# CatchTheLED.net
KiCad netlist of a schematic drawn in EAGLE
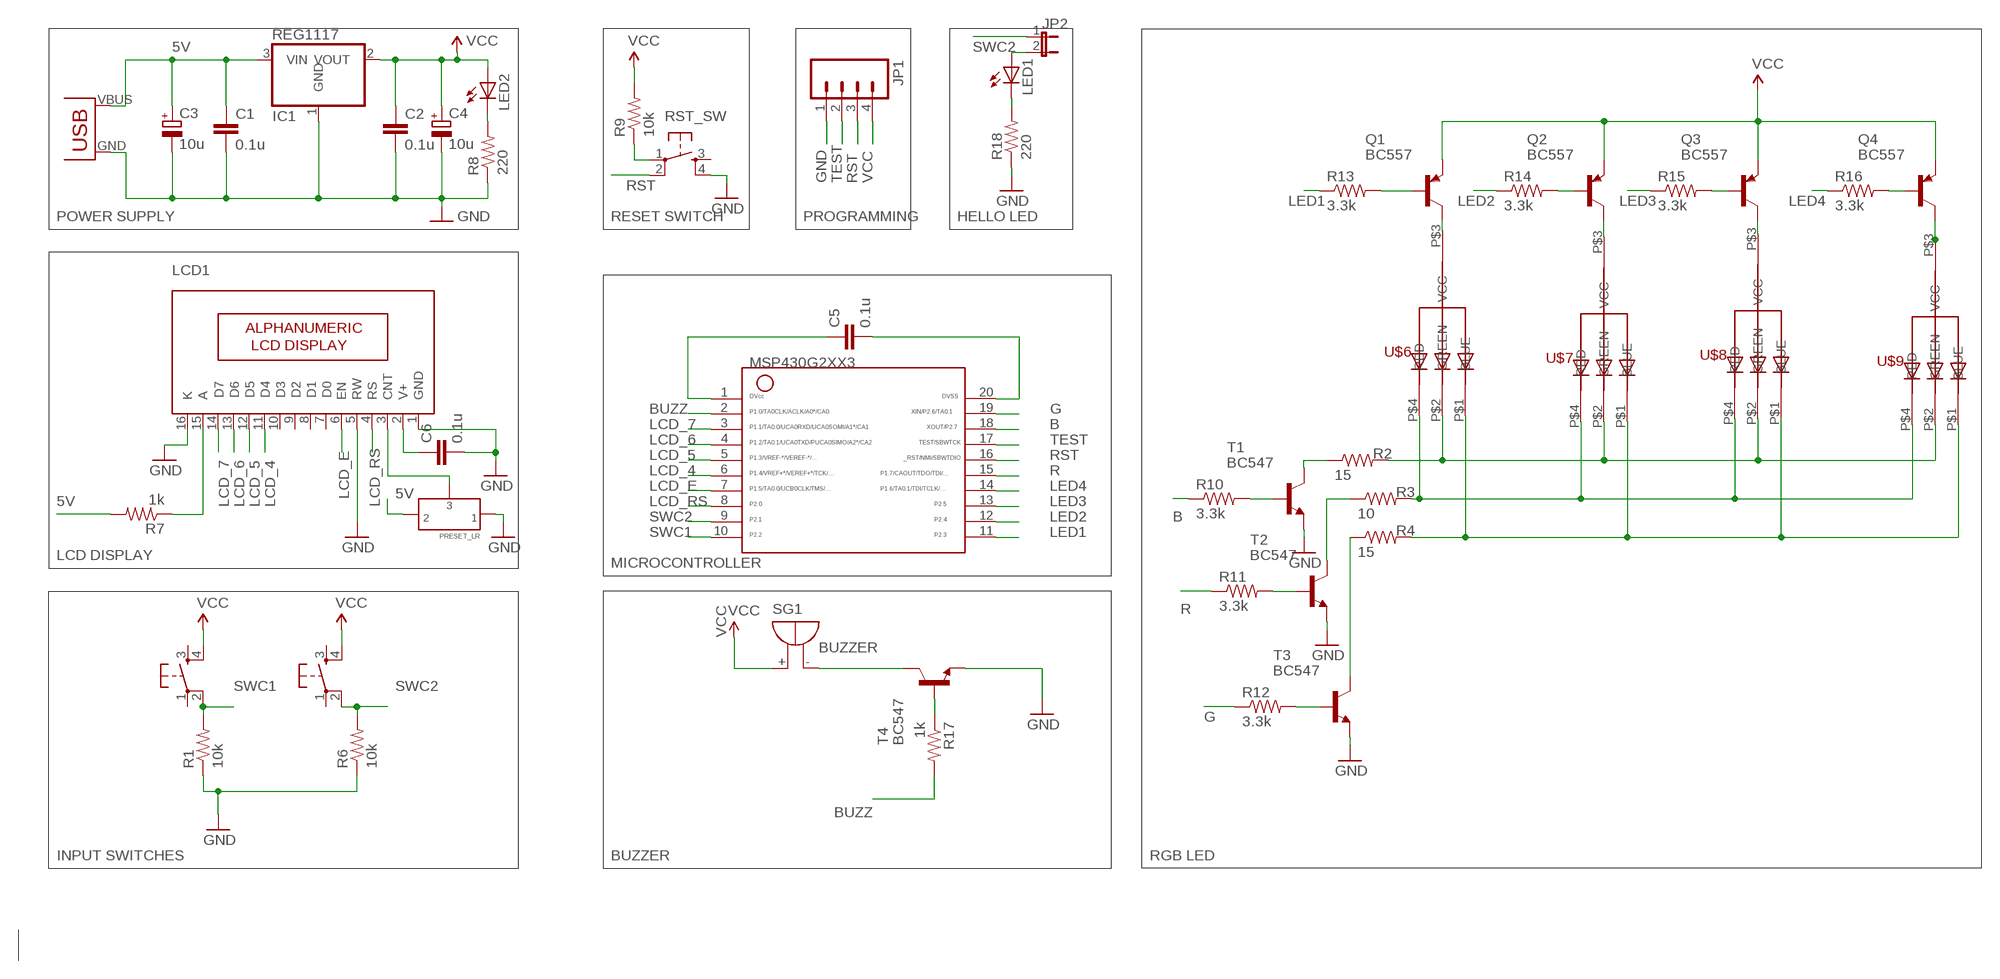
[diagram p0: schematic, sheet 1]

(export (version "E")
  (design (tool "Eeschema 10.0.6"))
  (components
    (comp (ref "C1")
      (value "0.1u")
      (footprint "eagle-import:C025-025X050")
      (libsource (lib "eagle-import") (part "C-EU025-025X050"))
    )
    (comp (ref "C2")
      (value "0.1u")
      (footprint "eagle-import:C025-025X050")
      (libsource (lib "eagle-import") (part "C-EU025-025X050"))
    )
    (comp (ref "C3")
      (value "10u")
      (footprint "eagle-import:E2,5-5")
      (libsource (lib "eagle-import") (part "CPOL-EUE2.5-5"))
    )
    (comp (ref "C4")
      (value "10u")
      (footprint "eagle-import:E2,5-5")
      (libsource (lib "eagle-import") (part "CPOL-EUE2.5-5"))
    )
    (comp (ref "C5")
      (value "0.1u")
      (footprint "eagle-import:C025-025X050")
      (libsource (lib "eagle-import") (part "C-EU025-025X050"))
    )
    (comp (ref "C6")
      (value "0.1u")
      (footprint "eagle-import:C025-025X050")
      (libsource (lib "eagle-import") (part "C-EU025-025X050"))
    )
    (comp (ref "IC1")
      (value "REG1117")
      (footprint "eagle-import:SOT223")
      (libsource (lib "eagle-import") (part "REG1117"))
    )
    (comp (ref "JP1")
      (value "M04")
      (footprint "eagle-import:04P")
      (libsource (lib "eagle-import") (part "M04"))
    )
    (comp (ref "JP2")
      (value "JP1E")
      (footprint "eagle-import:JP1")
      (libsource (lib "eagle-import") (part "JP1E"))
    )
    (comp (ref "LCD1")
      (value "16X2LCD")
      (footprint "eagle-import:16X2_LCD")
      (libsource (lib "eagle-import") (part "16X2LCD"))
    )
    (comp (ref "LED1")
      (value "LED3MM")
      (footprint "eagle-import:LED3MM")
      (libsource (lib "eagle-import") (part "LED3MM"))
    )
    (comp (ref "LED2")
      (value "LED3MM")
      (footprint "eagle-import:LED3MM")
      (libsource (lib "eagle-import") (part "LED3MM"))
    )
    (comp (ref "Q1")
      (value "BC557")
      (footprint "eagle-import:TO92")
      (libsource (lib "eagle-import") (part "BC557"))
    )
    (comp (ref "Q2")
      (value "BC557")
      (footprint "eagle-import:TO92")
      (libsource (lib "eagle-import") (part "BC557"))
    )
    (comp (ref "Q3")
      (value "BC557")
      (footprint "eagle-import:TO92")
      (libsource (lib "eagle-import") (part "BC557"))
    )
    (comp (ref "Q4")
      (value "BC557")
      (footprint "eagle-import:TO92")
      (libsource (lib "eagle-import") (part "BC557"))
    )
    (comp (ref "R1")
      (value "10k")
      (footprint "eagle-import:0207_7")
      (libsource (lib "eagle-import") (part "RESISTOR0207/7"))
    )
    (comp (ref "R2")
      (value "15")
      (footprint "eagle-import:0207_7")
      (libsource (lib "eagle-import") (part "RESISTOR0207/7"))
    )
    (comp (ref "R3")
      (value "10")
      (footprint "eagle-import:0207_7")
      (libsource (lib "eagle-import") (part "RESISTOR0207/7"))
    )
    (comp (ref "R4")
      (value "15")
      (footprint "eagle-import:0207_7")
      (libsource (lib "eagle-import") (part "RESISTOR0207/7"))
    )
    (comp (ref "R6")
      (value "10k")
      (footprint "eagle-import:0207_7")
      (libsource (lib "eagle-import") (part "RESISTOR0207/7"))
    )
    (comp (ref "R7")
      (value "1k")
      (footprint "eagle-import:0207_7")
      (libsource (lib "eagle-import") (part "RESISTOR0207/7"))
    )
    (comp (ref "R8")
      (value "220")
      (footprint "eagle-import:0207_7")
      (libsource (lib "eagle-import") (part "RESISTOR0207/7"))
    )
    (comp (ref "R9")
      (value "10k")
      (footprint "eagle-import:0207_7")
      (libsource (lib "eagle-import") (part "RESISTOR0207/7"))
    )
    (comp (ref "R10")
      (value "3.3k")
      (footprint "eagle-import:0207_7")
      (libsource (lib "eagle-import") (part "RESISTOR0207/7"))
    )
    (comp (ref "R11")
      (value "3.3k")
      (footprint "eagle-import:0207_7")
      (libsource (lib "eagle-import") (part "RESISTOR0207/7"))
    )
    (comp (ref "R12")
      (value "3.3k")
      (footprint "eagle-import:0207_7")
      (libsource (lib "eagle-import") (part "RESISTOR0207/7"))
    )
    (comp (ref "R13")
      (value "3.3k")
      (footprint "eagle-import:0207_7")
      (libsource (lib "eagle-import") (part "RESISTOR0207/7"))
    )
    (comp (ref "R14")
      (value "3.3k")
      (footprint "eagle-import:0207_7")
      (libsource (lib "eagle-import") (part "RESISTOR0207/7"))
    )
    (comp (ref "R15")
      (value "3.3k")
      (footprint "eagle-import:0207_7")
      (libsource (lib "eagle-import") (part "RESISTOR0207/7"))
    )
    (comp (ref "R16")
      (value "3.3k")
      (footprint "eagle-import:0207_7")
      (libsource (lib "eagle-import") (part "RESISTOR0207/7"))
    )
    (comp (ref "R17")
      (value "1k")
      (footprint "eagle-import:0207_7")
      (libsource (lib "eagle-import") (part "RESISTOR0207/7"))
    )
    (comp (ref "R18")
      (value "220")
      (footprint "eagle-import:0207_7")
      (libsource (lib "eagle-import") (part "RESISTOR0207/7"))
    )
    (comp (ref "RST_SW")
      (value "OMRON_SWITCH_10-XX")
      (footprint "eagle-import:B3F-10XX")
      (libsource (lib "eagle-import") (part "OMRON_SWITCH_10-XX"))
    )
    (comp (ref "SG1")
      (value "BUZZER")
      (footprint "eagle-import:F_TMB")
      (libsource (lib "eagle-import") (part "BUZZER"))
    )
    (comp (ref "T1")
      (value "BC547")
      (footprint "eagle-import:TO92")
      (libsource (lib "eagle-import") (part "BC547"))
    )
    (comp (ref "T2")
      (value "BC547")
      (footprint "eagle-import:TO92")
      (libsource (lib "eagle-import") (part "BC547"))
    )
    (comp (ref "T3")
      (value "BC547")
      (footprint "eagle-import:TO92")
      (libsource (lib "eagle-import") (part "BC547"))
    )
    (comp (ref "T4")
      (value "BC547")
      (footprint "eagle-import:TO92")
      (libsource (lib "eagle-import") (part "BC547"))
    )
    (comp (ref "U$1")
      (value "USB(POWER)")
      (footprint "eagle-import:USB(POWER)")
      (libsource (lib "eagle-import") (part "USB(POWER)"))
    )
    (comp (ref "U$2")
      (value "MSP430G2553DIP20")
      (footprint "eagle-import:G2553-DIP20")
      (libsource (lib "eagle-import") (part "MSP430G2553DIP20"))
    )
    (comp (ref "U$3")
      (value "OMRON_SWITCH_40-XX")
      (footprint "eagle-import:B3F-40XX")
      (libsource (lib "eagle-import") (part "OMRON_SWITCH_40-XX"))
    )
    (comp (ref "U$4")
      (value "OMRON_SWITCH_40-XX")
      (footprint "eagle-import:B3F-40XX")
      (libsource (lib "eagle-import") (part "OMRON_SWITCH_40-XX"))
    )
    (comp (ref "U$5")
      (value "PRESET_LR")
      (footprint "eagle-import:PRESET_LR")
      (libsource (lib "eagle-import") (part "PRESET_LR"))
    )
    (comp (ref "U$6")
      (value "5MMRGBLED")
      (footprint "eagle-import:LED5MMRGB")
      (libsource (lib "eagle-import") (part "5MMRGBLED"))
    )
    (comp (ref "U$7")
      (value "5MMRGBLED")
      (footprint "eagle-import:LED5MMRGB")
      (libsource (lib "eagle-import") (part "5MMRGBLED"))
    )
    (comp (ref "U$8")
      (value "5MMRGBLED")
      (footprint "eagle-import:LED5MMRGB")
      (libsource (lib "eagle-import") (part "5MMRGBLED"))
    )
    (comp (ref "U$9")
      (value "5MMRGBLED")
      (footprint "eagle-import:LED5MMRGB")
      (libsource (lib "eagle-import") (part "5MMRGBLED"))
    )
  )
  (nets
    (net (code "1") (name "/5V") (class "Default")
      (node (ref "C1") (pin "1") (pinfunction "1_1") (pintype "passive"))
      (node (ref "C3") (pin "+") (pinfunction "+_+") (pintype "passive"))
      (node (ref "C6") (pin "1") (pinfunction "1_1") (pintype "passive"))
      (node (ref "IC1") (pin "3") (pinfunction "VIN_3") (pintype "input"))
      (node (ref "LCD1") (pin "2") (pinfunction "V+_2") (pintype "bidirectional"))
      (node (ref "R7") (pin "2") (pinfunction "2_2") (pintype "passive"))
      (node (ref "U$1") (pin "VBUS") (pinfunction "VCC_VBUS") (pintype "power_in"))
      (node (ref "U$5") (pin "P$2") (pinfunction "2_P$2") (pintype "passive"))
    )
    (net (code "2") (name "/B") (class "Default")
      (node (ref "R10") (pin "1") (pinfunction "1_1") (pintype "passive"))
      (node (ref "U$2") (pin "18") (pinfunction "18_18") (pintype "bidirectional"))
    )
    (net (code "3") (name "/BUZZ") (class "Default")
      (node (ref "R17") (pin "2") (pinfunction "2_2") (pintype "passive"))
      (node (ref "U$2") (pin "2") (pinfunction "2_2") (pintype "bidirectional"))
    )
    (net (code "4") (name "/G") (class "Default")
      (node (ref "R12") (pin "1") (pinfunction "1_1") (pintype "passive"))
      (node (ref "U$2") (pin "19") (pinfunction "19_19") (pintype "bidirectional"))
    )
    (net (code "5") (name "/LCD_4") (class "Default")
      (node (ref "LCD1") (pin "11") (pinfunction "D4_11") (pintype "bidirectional"))
      (node (ref "U$2") (pin "6") (pinfunction "6_6") (pintype "bidirectional"))
    )
    (net (code "6") (name "/LCD_5") (class "Default")
      (node (ref "LCD1") (pin "12") (pinfunction "D5_12") (pintype "bidirectional"))
      (node (ref "U$2") (pin "5") (pinfunction "5_5") (pintype "bidirectional"))
    )
    (net (code "7") (name "/LCD_6") (class "Default")
      (node (ref "LCD1") (pin "13") (pinfunction "D6_13") (pintype "bidirectional"))
      (node (ref "U$2") (pin "4") (pinfunction "4_4") (pintype "bidirectional"))
    )
    (net (code "8") (name "/LCD_7") (class "Default")
      (node (ref "LCD1") (pin "14") (pinfunction "D7_14") (pintype "bidirectional"))
      (node (ref "U$2") (pin "3") (pinfunction "3_3") (pintype "bidirectional"))
    )
    (net (code "9") (name "/LCD_E") (class "Default")
      (node (ref "LCD1") (pin "6") (pinfunction "EN_6") (pintype "bidirectional"))
      (node (ref "U$2") (pin "7") (pinfunction "7_7") (pintype "bidirectional"))
    )
    (net (code "10") (name "/LCD_RS") (class "Default")
      (node (ref "LCD1") (pin "4") (pinfunction "RS_4") (pintype "bidirectional"))
      (node (ref "U$2") (pin "8") (pinfunction "8_8") (pintype "bidirectional"))
    )
    (net (code "11") (name "/LED1") (class "Default")
      (node (ref "R13") (pin "1") (pinfunction "1_1") (pintype "passive"))
      (node (ref "U$2") (pin "11") (pinfunction "11_11") (pintype "bidirectional"))
    )
    (net (code "12") (name "/LED2") (class "Default")
      (node (ref "R14") (pin "1") (pinfunction "1_1") (pintype "passive"))
      (node (ref "U$2") (pin "12") (pinfunction "12_12") (pintype "bidirectional"))
    )
    (net (code "13") (name "/LED3") (class "Default")
      (node (ref "R15") (pin "1") (pinfunction "1_1") (pintype "passive"))
      (node (ref "U$2") (pin "13") (pinfunction "13_13") (pintype "bidirectional"))
    )
    (net (code "14") (name "/LED4") (class "Default")
      (node (ref "R16") (pin "1") (pinfunction "1_1") (pintype "passive"))
      (node (ref "U$2") (pin "14") (pinfunction "14_14") (pintype "bidirectional"))
    )
    (net (code "15") (name "/R") (class "Default")
      (node (ref "R11") (pin "1") (pinfunction "1_1") (pintype "passive"))
      (node (ref "U$2") (pin "15") (pinfunction "15_15") (pintype "bidirectional"))
    )
    (net (code "16") (name "/RST") (class "Default")
      (node (ref "JP1") (pin "3") (pinfunction "3_3") (pintype "passive"))
      (node (ref "RST_SW") (pin "2") (pinfunction "P1_2") (pintype "passive"))
      (node (ref "U$2") (pin "16") (pinfunction "16_16") (pintype "bidirectional"))
    )
    (net (code "17") (name "/SWC1") (class "Default")
      (node (ref "R1") (pin "2") (pinfunction "2_2") (pintype "passive"))
      (node (ref "U$2") (pin "10") (pinfunction "10_10") (pintype "bidirectional"))
      (node (ref "U$3") (pin "2") (pinfunction "P1_2") (pintype "passive"))
    )
    (net (code "18") (name "/SWC2") (class "Default")
      (node (ref "JP2") (pin "1") (pinfunction "1_1") (pintype "passive"))
      (node (ref "R6") (pin "2") (pinfunction "2_2") (pintype "passive"))
      (node (ref "U$2") (pin "9") (pinfunction "9_9") (pintype "bidirectional"))
      (node (ref "U$4") (pin "2") (pinfunction "P1_2") (pintype "passive"))
    )
    (net (code "19") (name "/TEST") (class "Default")
      (node (ref "JP1") (pin "2") (pinfunction "2_2") (pintype "passive"))
      (node (ref "U$2") (pin "17") (pinfunction "17_17") (pintype "bidirectional"))
    )
    (net (code "20") (name "GND") (class "Default")
      (node (ref "C1") (pin "2") (pinfunction "2_2") (pintype "passive"))
      (node (ref "C2") (pin "2") (pinfunction "2_2") (pintype "passive"))
      (node (ref "C3") (pin "-") (pinfunction "-_-") (pintype "passive"))
      (node (ref "C4") (pin "-") (pinfunction "-_-") (pintype "passive"))
      (node (ref "C5") (pin "2") (pinfunction "2_2") (pintype "passive"))
      (node (ref "C6") (pin "2") (pinfunction "2_2") (pintype "passive"))
      (node (ref "IC1") (pin "1") (pinfunction "GND_1") (pintype "power_in"))
      (node (ref "JP1") (pin "1") (pinfunction "1_1") (pintype "passive"))
      (node (ref "LCD1") (pin "1") (pinfunction "GND_1") (pintype "bidirectional"))
      (node (ref "LCD1") (pin "16") (pinfunction "K_16") (pintype "bidirectional"))
      (node (ref "LCD1") (pin "5") (pinfunction "RW_5") (pintype "bidirectional"))
      (node (ref "R1") (pin "1") (pinfunction "1_1") (pintype "passive"))
      (node (ref "R18") (pin "1") (pinfunction "1_1") (pintype "passive"))
      (node (ref "R6") (pin "1") (pinfunction "1_1") (pintype "passive"))
      (node (ref "R8") (pin "1") (pinfunction "1_1") (pintype "passive"))
      (node (ref "RST_SW") (pin "4") (pinfunction "S1_4") (pintype "passive"))
      (node (ref "T1") (pin "1") (pinfunction "E_1") (pintype "passive"))
      (node (ref "T2") (pin "1") (pinfunction "E_1") (pintype "passive"))
      (node (ref "T3") (pin "1") (pinfunction "E_1") (pintype "passive"))
      (node (ref "T4") (pin "1") (pinfunction "E_1") (pintype "passive"))
      (node (ref "U$1") (pin "GND") (pinfunction "GND_GND") (pintype "power_in"))
      (node (ref "U$2") (pin "20") (pinfunction "20_20") (pintype "power_in"))
      (node (ref "U$5") (pin "P$1") (pinfunction "1_P$1") (pintype "passive"))
    )
    (net (code "21") (name "Net-(JP2-Pad2)") (class "Default")
      (node (ref "JP2") (pin "2") (pinfunction "2_2") (pintype "passive"))
      (node (ref "LED1") (pin "A") (pinfunction "A_A") (pintype "passive"))
    )
    (net (code "22") (name "Net-(LCD1-A)") (class "Default")
      (node (ref "LCD1") (pin "15") (pinfunction "A_15") (pintype "bidirectional"))
      (node (ref "R7") (pin "1") (pinfunction "1_1") (pintype "passive"))
    )
    (net (code "23") (name "Net-(LCD1-CNT)") (class "Default")
      (node (ref "LCD1") (pin "3") (pinfunction "CNT_3") (pintype "bidirectional"))
      (node (ref "U$5") (pin "P$3") (pinfunction "3_P$3") (pintype "passive"))
    )
    (net (code "24") (name "Net-(LED1-C)") (class "Default")
      (node (ref "LED1") (pin "K") (pinfunction "C_K") (pintype "passive"))
      (node (ref "R18") (pin "2") (pinfunction "2_2") (pintype "passive"))
    )
    (net (code "25") (name "Net-(LED2-C)") (class "Default")
      (node (ref "LED2") (pin "K") (pinfunction "C_K") (pintype "passive"))
      (node (ref "R8") (pin "2") (pinfunction "2_2") (pintype "passive"))
    )
    (net (code "26") (name "Net-(Q1-B)") (class "Default")
      (node (ref "Q1") (pin "2") (pinfunction "B_2") (pintype "passive"))
      (node (ref "R13") (pin "2") (pinfunction "2_2") (pintype "passive"))
    )
    (net (code "27") (name "Net-(Q1-C)") (class "Default")
      (node (ref "Q1") (pin "3") (pinfunction "C_3") (pintype "passive"))
      (node (ref "U$6") (pin "P$3") (pinfunction "VCC_P$3") (pintype "bidirectional"))
    )
    (net (code "28") (name "Net-(Q2-B)") (class "Default")
      (node (ref "Q2") (pin "2") (pinfunction "B_2") (pintype "passive"))
      (node (ref "R14") (pin "2") (pinfunction "2_2") (pintype "passive"))
    )
    (net (code "29") (name "Net-(Q2-C)") (class "Default")
      (node (ref "Q2") (pin "3") (pinfunction "C_3") (pintype "passive"))
      (node (ref "U$7") (pin "P$3") (pinfunction "VCC_P$3") (pintype "bidirectional"))
    )
    (net (code "30") (name "Net-(Q3-B)") (class "Default")
      (node (ref "Q3") (pin "2") (pinfunction "B_2") (pintype "passive"))
      (node (ref "R15") (pin "2") (pinfunction "2_2") (pintype "passive"))
    )
    (net (code "31") (name "Net-(Q3-C)") (class "Default")
      (node (ref "Q3") (pin "3") (pinfunction "C_3") (pintype "passive"))
      (node (ref "U$8") (pin "P$3") (pinfunction "VCC_P$3") (pintype "bidirectional"))
    )
    (net (code "32") (name "Net-(Q4-B)") (class "Default")
      (node (ref "Q4") (pin "2") (pinfunction "B_2") (pintype "passive"))
      (node (ref "R16") (pin "2") (pinfunction "2_2") (pintype "passive"))
    )
    (net (code "33") (name "Net-(Q4-C)") (class "Default")
      (node (ref "Q4") (pin "3") (pinfunction "C_3") (pintype "passive"))
      (node (ref "U$9") (pin "P$3") (pinfunction "VCC_P$3") (pintype "bidirectional"))
    )
    (net (code "34") (name "Net-(RST_SW-P)") (class "Default")
      (node (ref "R9") (pin "1") (pinfunction "1_1") (pintype "passive"))
      (node (ref "RST_SW") (pin "1") (pinfunction "P_1") (pintype "passive"))
    )
    (net (code "35") (name "Net-(T1-B)") (class "Default")
      (node (ref "R10") (pin "2") (pinfunction "2_2") (pintype "passive"))
      (node (ref "T1") (pin "2") (pinfunction "B_2") (pintype "passive"))
    )
    (net (code "36") (name "Net-(T1-C)") (class "Default")
      (node (ref "R2") (pin "1") (pinfunction "1_1") (pintype "passive"))
      (node (ref "T1") (pin "3") (pinfunction "C_3") (pintype "passive"))
    )
    (net (code "37") (name "Net-(T2-B)") (class "Default")
      (node (ref "R11") (pin "2") (pinfunction "2_2") (pintype "passive"))
      (node (ref "T2") (pin "2") (pinfunction "B_2") (pintype "passive"))
    )
    (net (code "38") (name "Net-(T2-C)") (class "Default")
      (node (ref "R3") (pin "1") (pinfunction "1_1") (pintype "passive"))
      (node (ref "T2") (pin "3") (pinfunction "C_3") (pintype "passive"))
    )
    (net (code "39") (name "Net-(T3-B)") (class "Default")
      (node (ref "R12") (pin "2") (pinfunction "2_2") (pintype "passive"))
      (node (ref "T3") (pin "2") (pinfunction "B_2") (pintype "passive"))
    )
    (net (code "40") (name "Net-(T3-C)") (class "Default")
      (node (ref "R4") (pin "1") (pinfunction "1_1") (pintype "passive"))
      (node (ref "T3") (pin "3") (pinfunction "C_3") (pintype "passive"))
    )
    (net (code "41") (name "Net-(T4-B)") (class "Default")
      (node (ref "R17") (pin "1") (pinfunction "1_1") (pintype "passive"))
      (node (ref "T4") (pin "2") (pinfunction "B_2") (pintype "passive"))
    )
    (net (code "42") (name "Net-(T4-C)") (class "Default")
      (node (ref "SG1") (pin "-") (pinfunction "-_-") (pintype "passive"))
      (node (ref "T4") (pin "3") (pinfunction "C_3") (pintype "passive"))
    )
    (net (code "43") (name "Net-(U$6-BLUE)") (class "Default")
      (node (ref "R4") (pin "2") (pinfunction "2_2") (pintype "passive"))
      (node (ref "U$6") (pin "P$1") (pinfunction "BLUE_P$1") (pintype "bidirectional"))
      (node (ref "U$7") (pin "P$1") (pinfunction "BLUE_P$1") (pintype "bidirectional"))
      (node (ref "U$8") (pin "P$1") (pinfunction "BLUE_P$1") (pintype "bidirectional"))
      (node (ref "U$9") (pin "P$1") (pinfunction "BLUE_P$1") (pintype "bidirectional"))
    )
    (net (code "44") (name "Net-(U$6-GREEN)") (class "Default")
      (node (ref "R2") (pin "2") (pinfunction "2_2") (pintype "passive"))
      (node (ref "U$6") (pin "P$2") (pinfunction "GREEN_P$2") (pintype "bidirectional"))
      (node (ref "U$7") (pin "P$2") (pinfunction "GREEN_P$2") (pintype "bidirectional"))
      (node (ref "U$8") (pin "P$2") (pinfunction "GREEN_P$2") (pintype "bidirectional"))
      (node (ref "U$9") (pin "P$2") (pinfunction "GREEN_P$2") (pintype "bidirectional"))
    )
    (net (code "45") (name "Net-(U$6-RED)") (class "Default")
      (node (ref "R3") (pin "2") (pinfunction "2_2") (pintype "passive"))
      (node (ref "U$6") (pin "P$4") (pinfunction "RED_P$4") (pintype "bidirectional"))
      (node (ref "U$7") (pin "P$4") (pinfunction "RED_P$4") (pintype "bidirectional"))
      (node (ref "U$8") (pin "P$4") (pinfunction "RED_P$4") (pintype "bidirectional"))
      (node (ref "U$9") (pin "P$4") (pinfunction "RED_P$4") (pintype "bidirectional"))
    )
    (net (code "46") (name "VCC") (class "Default")
      (node (ref "C2") (pin "1") (pinfunction "1_1") (pintype "passive"))
      (node (ref "C4") (pin "+") (pinfunction "+_+") (pintype "passive"))
      (node (ref "C5") (pin "1") (pinfunction "1_1") (pintype "passive"))
      (node (ref "IC1") (pin "2") (pinfunction "VOUT_2") (pintype "output"))
      (node (ref "JP1") (pin "4") (pinfunction "4_4") (pintype "passive"))
      (node (ref "LED2") (pin "A") (pinfunction "A_A") (pintype "passive"))
      (node (ref "Q1") (pin "1") (pinfunction "E_1") (pintype "passive"))
      (node (ref "Q2") (pin "1") (pinfunction "E_1") (pintype "passive"))
      (node (ref "Q3") (pin "1") (pinfunction "E_1") (pintype "passive"))
      (node (ref "Q4") (pin "1") (pinfunction "E_1") (pintype "passive"))
      (node (ref "R9") (pin "2") (pinfunction "2_2") (pintype "passive"))
      (node (ref "SG1") (pin "+") (pinfunction "+_+") (pintype "passive"))
      (node (ref "U$2") (pin "1") (pinfunction "1_1") (pintype "power_in"))
      (node (ref "U$3") (pin "4") (pinfunction "S1_4") (pintype "passive"))
      (node (ref "U$4") (pin "4") (pinfunction "S1_4") (pintype "passive"))
    )
    (net (code "47") (name "unconnected-(LCD1-D0-Pad7)") (class "Default")
      (node (ref "LCD1") (pin "7") (pinfunction "D0_7") (pintype "bidirectional"))
    )
    (net (code "48") (name "unconnected-(LCD1-D1-Pad8)") (class "Default")
      (node (ref "LCD1") (pin "8") (pinfunction "D1_8") (pintype "bidirectional"))
    )
    (net (code "49") (name "unconnected-(LCD1-D2-Pad9)") (class "Default")
      (node (ref "LCD1") (pin "9") (pinfunction "D2_9") (pintype "bidirectional"))
    )
    (net (code "50") (name "unconnected-(LCD1-D3-Pad10)") (class "Default")
      (node (ref "LCD1") (pin "10") (pinfunction "D3_10") (pintype "bidirectional"))
    )
    (net (code "51") (name "unconnected-(RST_SW-S-Pad3)") (class "Default")
      (node (ref "RST_SW") (pin "3") (pinfunction "S_3") (pintype "passive"))
    )
    (net (code "52") (name "unconnected-(U$3-P-Pad1)") (class "Default")
      (node (ref "U$3") (pin "1") (pinfunction "P_1") (pintype "passive"))
    )
    (net (code "53") (name "unconnected-(U$3-S-Pad3)") (class "Default")
      (node (ref "U$3") (pin "3") (pinfunction "S_3") (pintype "passive"))
    )
    (net (code "54") (name "unconnected-(U$4-P-Pad1)") (class "Default")
      (node (ref "U$4") (pin "1") (pinfunction "P_1") (pintype "passive"))
    )
    (net (code "55") (name "unconnected-(U$4-S-Pad3)") (class "Default")
      (node (ref "U$4") (pin "3") (pinfunction "S_3") (pintype "passive"))
    )
  )
)
